# MainBoard.net
KiCad netlist of a schematic drawn in EAGLE
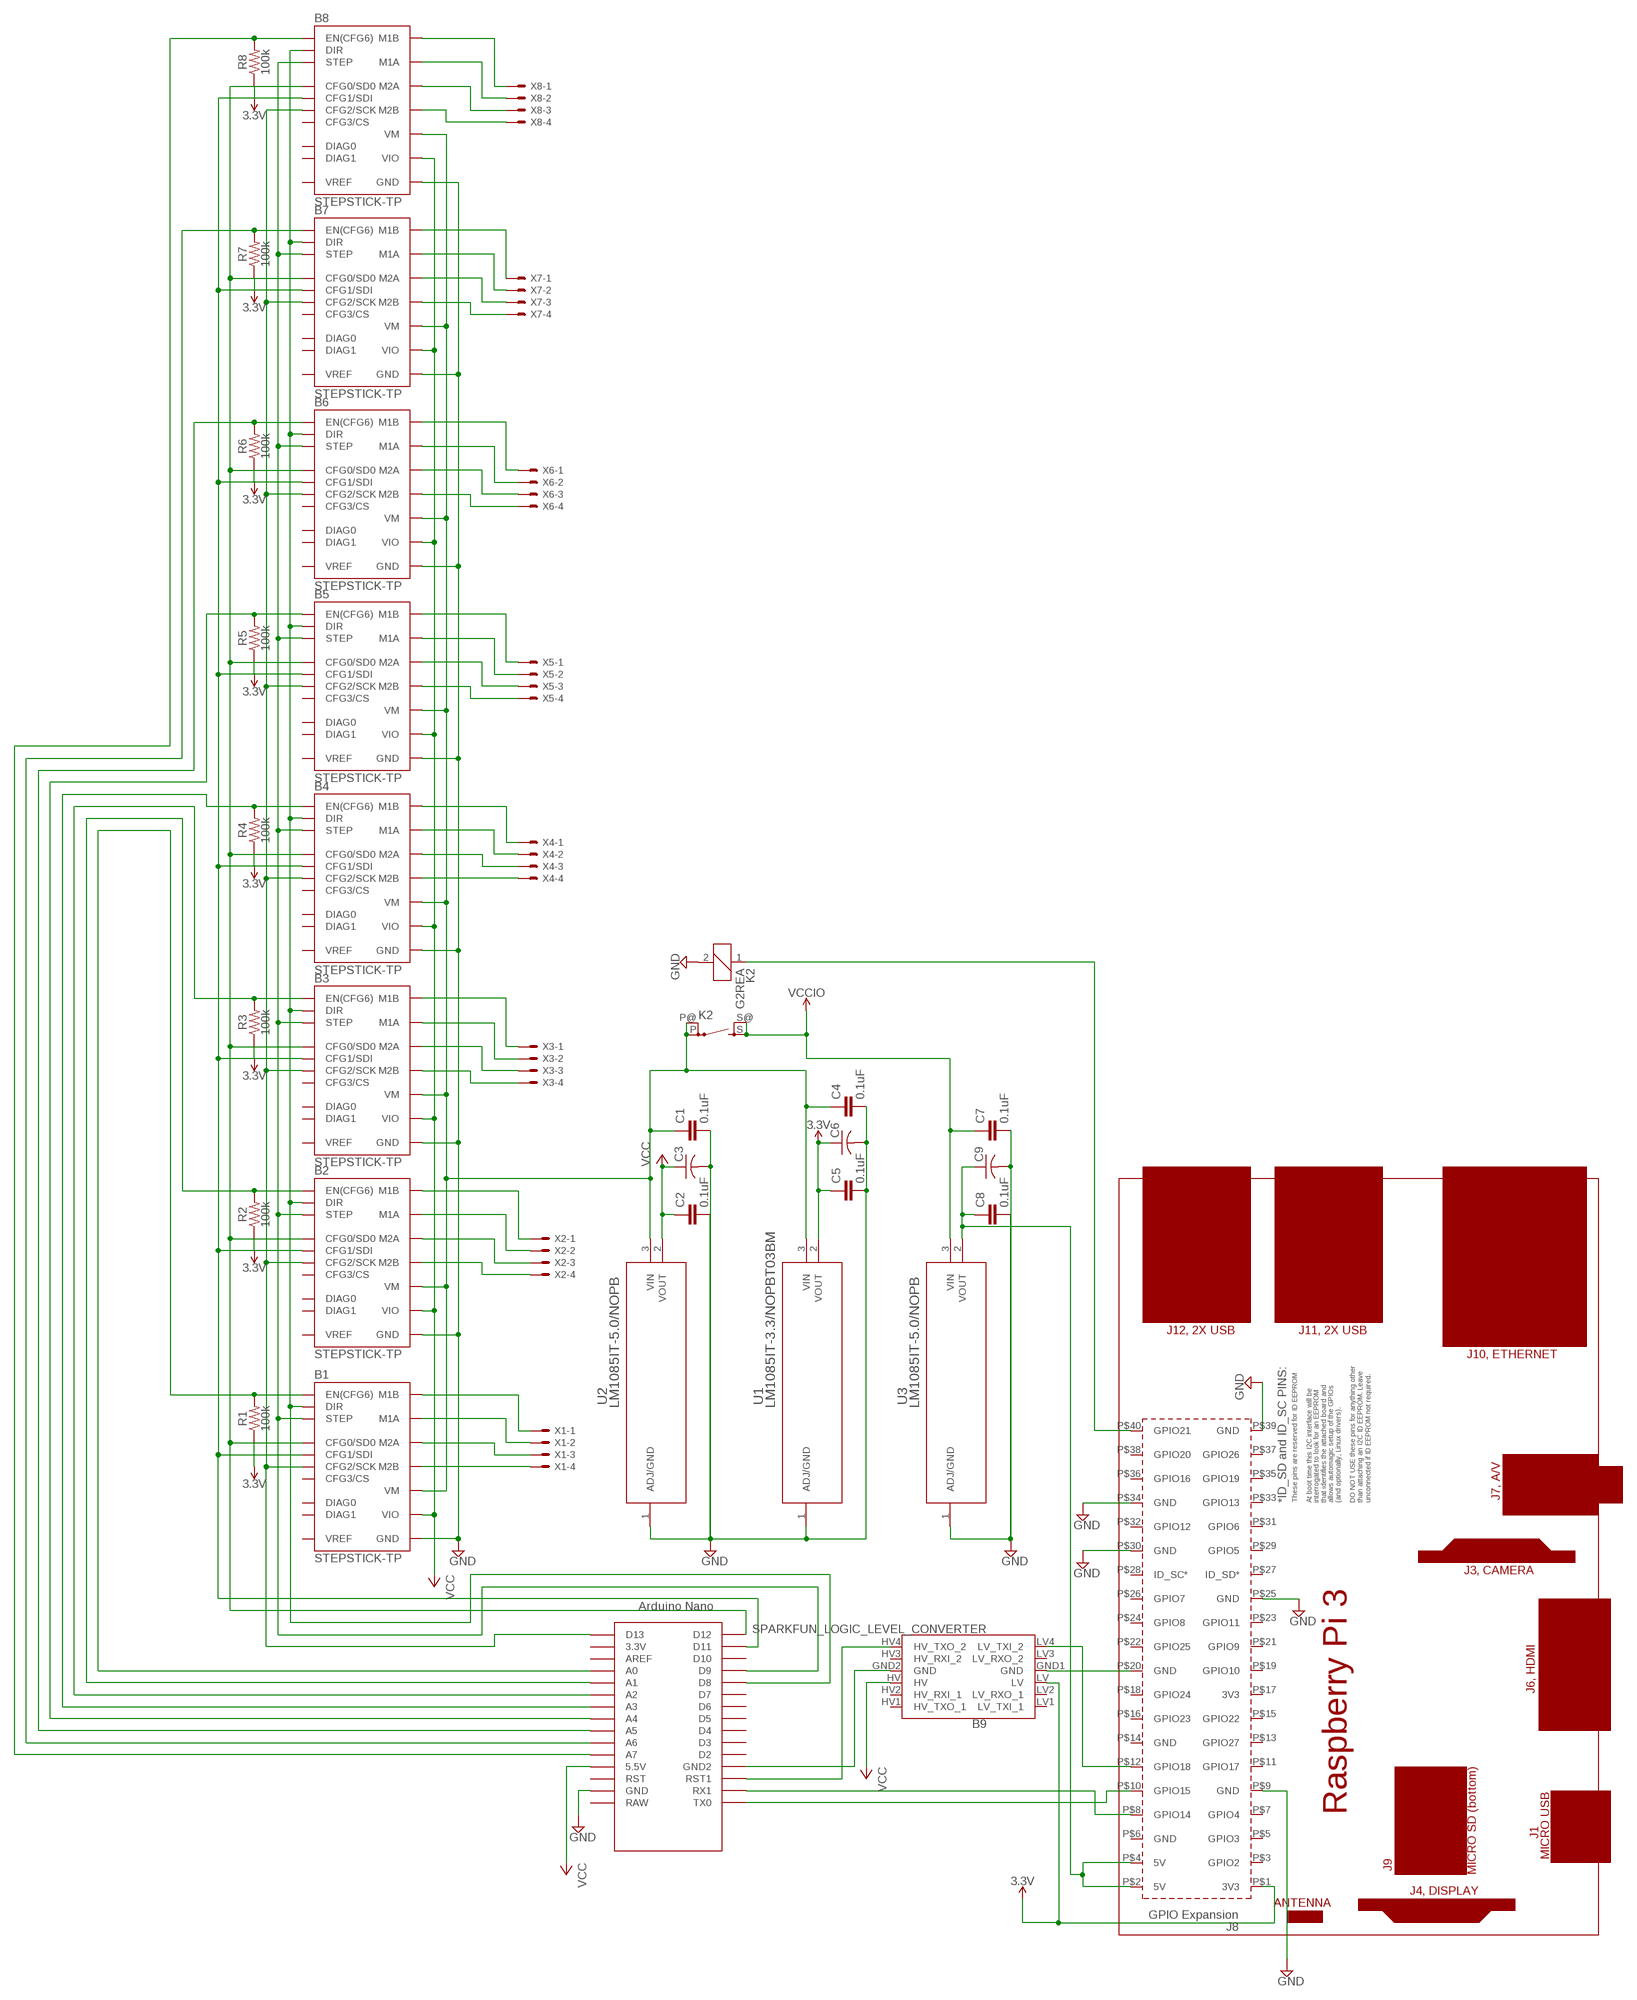
[diagram p0: schematic, sheet 1]

(export (version "E")
  (design (tool "Eeschema 10.0.6"))
  (components
    (comp (ref "B1")
      (value "STEPSTICK-TP")
      (footprint "eagle-import:STEPSTICK_TP")
      (libsource (lib "eagle-import") (part "STEPSTICK-TP"))
    )
    (comp (ref "B2")
      (value "STEPSTICK-TP")
      (footprint "eagle-import:STEPSTICK_TP")
      (libsource (lib "eagle-import") (part "STEPSTICK-TP"))
    )
    (comp (ref "B3")
      (value "STEPSTICK-TP")
      (footprint "eagle-import:STEPSTICK_TP")
      (libsource (lib "eagle-import") (part "STEPSTICK-TP"))
    )
    (comp (ref "B4")
      (value "STEPSTICK-TP")
      (footprint "eagle-import:STEPSTICK_TP")
      (libsource (lib "eagle-import") (part "STEPSTICK-TP"))
    )
    (comp (ref "B5")
      (value "STEPSTICK-TP")
      (footprint "eagle-import:STEPSTICK_TP")
      (libsource (lib "eagle-import") (part "STEPSTICK-TP"))
    )
    (comp (ref "B6")
      (value "STEPSTICK-TP")
      (footprint "eagle-import:STEPSTICK_TP")
      (libsource (lib "eagle-import") (part "STEPSTICK-TP"))
    )
    (comp (ref "B7")
      (value "STEPSTICK-TP")
      (footprint "eagle-import:STEPSTICK_TP")
      (libsource (lib "eagle-import") (part "STEPSTICK-TP"))
    )
    (comp (ref "B8")
      (value "STEPSTICK-TP")
      (footprint "eagle-import:STEPSTICK_TP")
      (libsource (lib "eagle-import") (part "STEPSTICK-TP"))
    )
    (comp (ref "B9")
      (value "SPARKFUN_LOGIC_LEVEL_CONVERTER")
      (footprint "eagle-import:SPARKFUN_LOGIC_LEVEL_CONVERTER")
      (libsource (lib "eagle-import") (part "SPARKFUN_LOGIC_LEVEL_CONVERTER"))
    )
    (comp (ref "C1")
      (value "0.1uF")
      (footprint "eagle-import:CAP-PTH-SMALL-KIT")
      (libsource (lib "eagle-import") (part "0.1UF-KIT-EZ-50V-20%"))
    )
    (comp (ref "C2")
      (value "0.1uF")
      (footprint "eagle-import:CAP-PTH-SMALL-KIT")
      (libsource (lib "eagle-import") (part "0.1UF-KIT-EZ-50V-20%"))
    )
    (comp (ref "C3")
      (value "C-US025-050X050")
      (footprint "eagle-import:C025-050X050")
      (libsource (lib "eagle-import") (part "C-US025-050X050"))
    )
    (comp (ref "C4")
      (value "0.1uF")
      (footprint "eagle-import:CAP-PTH-SMALL-KIT")
      (libsource (lib "eagle-import") (part "0.1UF-KIT-EZ-50V-20%"))
    )
    (comp (ref "C5")
      (value "0.1uF")
      (footprint "eagle-import:CAP-PTH-SMALL-KIT")
      (libsource (lib "eagle-import") (part "0.1UF-KIT-EZ-50V-20%"))
    )
    (comp (ref "C6")
      (value "C-US025-050X050")
      (footprint "eagle-import:C025-050X050")
      (libsource (lib "eagle-import") (part "C-US025-050X050"))
    )
    (comp (ref "C7")
      (value "0.1uF")
      (footprint "eagle-import:CAP-PTH-SMALL-KIT")
      (libsource (lib "eagle-import") (part "0.1UF-KIT-EZ-50V-20%"))
    )
    (comp (ref "C8")
      (value "0.1uF")
      (footprint "eagle-import:CAP-PTH-SMALL-KIT")
      (libsource (lib "eagle-import") (part "0.1UF-KIT-EZ-50V-20%"))
    )
    (comp (ref "C9")
      (value "C-US025-050X050")
      (footprint "eagle-import:C025-050X050")
      (libsource (lib "eagle-import") (part "C-US025-050X050"))
    )
    (comp (ref "K2")
      (value "G2REA")
      (footprint "eagle-import:G2REA")
      (libsource (lib "eagle-import") (part "G2REA"))
    )
    (comp (ref "PCB1")
      (value "RPI3")
      (footprint "eagle-import:RPI3")
      (libsource (lib "eagle-import") (part "RPI3"))
    )
    (comp (ref "R1")
      (value "100k")
      (footprint "eagle-import:AXIAL-0.3-KIT")
      (libsource (lib "eagle-import") (part "100KOHM-HORIZ_KIT-1/4W-5%"))
    )
    (comp (ref "R2")
      (value "100k")
      (footprint "eagle-import:AXIAL-0.3-KIT")
      (libsource (lib "eagle-import") (part "100KOHM-HORIZ_KIT-1/4W-5%"))
    )
    (comp (ref "R3")
      (value "100k")
      (footprint "eagle-import:AXIAL-0.3-KIT")
      (libsource (lib "eagle-import") (part "100KOHM-HORIZ_KIT-1/4W-5%"))
    )
    (comp (ref "R4")
      (value "100k")
      (footprint "eagle-import:AXIAL-0.3-KIT")
      (libsource (lib "eagle-import") (part "100KOHM-HORIZ_KIT-1/4W-5%"))
    )
    (comp (ref "R5")
      (value "100k")
      (footprint "eagle-import:AXIAL-0.3-KIT")
      (libsource (lib "eagle-import") (part "100KOHM-HORIZ_KIT-1/4W-5%"))
    )
    (comp (ref "R6")
      (value "100k")
      (footprint "eagle-import:AXIAL-0.3-KIT")
      (libsource (lib "eagle-import") (part "100KOHM-HORIZ_KIT-1/4W-5%"))
    )
    (comp (ref "R7")
      (value "100k")
      (footprint "eagle-import:AXIAL-0.3-KIT")
      (libsource (lib "eagle-import") (part "100KOHM-HORIZ_KIT-1/4W-5%"))
    )
    (comp (ref "R8")
      (value "100k")
      (footprint "eagle-import:AXIAL-0.3-KIT")
      (libsource (lib "eagle-import") (part "100KOHM-HORIZ_KIT-1/4W-5%"))
    )
    (comp (ref "U$1")
      (value "NANO")
      (footprint "eagle-import:NANO")
      (libsource (lib "eagle-import") (part "NANO"))
    )
    (comp (ref "U1")
      (value "LM1085IT-3.3/NOPBT03BM")
      (footprint "eagle-import:T03BM")
      (fields (field (name "MANUFACTURER_PART_NUMBER") "LM1085IT3.3NOPB"))
      (libsource (lib "eagle-import") (part "LM1085IT-3.3/NOPBT03BM"))
    )
    (comp (ref "U2")
      (value "LM1085IT-5.0/NOPB")
      (footprint "eagle-import:T03B")
      (fields (field (name "MANUFACTURER_PART_NUMBER") "LM1085IT5.0NOPB"))
      (libsource (lib "eagle-import") (part "LM1085IT-5.0/NOPB"))
    )
    (comp (ref "U3")
      (value "LM1085IT-5.0/NOPB")
      (footprint "eagle-import:T03B")
      (fields (field (name "MANUFACTURER_PART_NUMBER") "LM1085IT5.0NOPB"))
      (libsource (lib "eagle-import") (part "LM1085IT-5.0/NOPB"))
    )
    (comp (ref "X1")
      (value "KK-156-4")
      (footprint "eagle-import:KK-156-4")
      (fields (field (name "MF") "MOLEX"))
      (libsource (lib "eagle-import") (part "KK-156-4"))
    )
    (comp (ref "X2")
      (value "KK-156-4")
      (footprint "eagle-import:KK-156-4")
      (fields (field (name "MF") "MOLEX"))
      (libsource (lib "eagle-import") (part "KK-156-4"))
    )
    (comp (ref "X3")
      (value "KK-156-4")
      (footprint "eagle-import:KK-156-4")
      (fields (field (name "MF") "MOLEX"))
      (libsource (lib "eagle-import") (part "KK-156-4"))
    )
    (comp (ref "X4")
      (value "KK-156-4")
      (footprint "eagle-import:KK-156-4")
      (fields (field (name "MF") "MOLEX"))
      (libsource (lib "eagle-import") (part "KK-156-4"))
    )
    (comp (ref "X5")
      (value "KK-156-4")
      (footprint "eagle-import:KK-156-4")
      (fields (field (name "MF") "MOLEX"))
      (libsource (lib "eagle-import") (part "KK-156-4"))
    )
    (comp (ref "X6")
      (value "KK-156-4")
      (footprint "eagle-import:KK-156-4")
      (fields (field (name "MF") "MOLEX"))
      (libsource (lib "eagle-import") (part "KK-156-4"))
    )
    (comp (ref "X7")
      (value "KK-156-4")
      (footprint "eagle-import:KK-156-4")
      (fields (field (name "MF") "MOLEX"))
      (libsource (lib "eagle-import") (part "KK-156-4"))
    )
    (comp (ref "X8")
      (value "KK-156-4")
      (footprint "eagle-import:KK-156-4")
      (fields (field (name "MF") "MOLEX"))
      (libsource (lib "eagle-import") (part "KK-156-4"))
    )
  )
  (nets
    (net (code "1") (name "3.3V") (class "Default")
      (node (ref "B9") (pin "LV") (pinfunction "LV_LV") (pintype "power_in"))
      (node (ref "C5") (pin "1") (pinfunction "1_1") (pintype "passive"))
      (node (ref "C6") (pin "1") (pinfunction "1_1") (pintype "passive"))
      (node (ref "PCB1") (pin "P$1") (pinfunction "3V3_P$1") (pintype "bidirectional"))
      (node (ref "R1") (pin "P$1") (pinfunction "1_P$1") (pintype "passive"))
      (node (ref "R2") (pin "P$1") (pinfunction "1_P$1") (pintype "passive"))
      (node (ref "R3") (pin "P$1") (pinfunction "1_P$1") (pintype "passive"))
      (node (ref "R4") (pin "P$1") (pinfunction "1_P$1") (pintype "passive"))
      (node (ref "R5") (pin "P$1") (pinfunction "1_P$1") (pintype "passive"))
      (node (ref "R6") (pin "P$1") (pinfunction "1_P$1") (pintype "passive"))
      (node (ref "R7") (pin "P$1") (pinfunction "1_P$1") (pintype "passive"))
      (node (ref "R8") (pin "P$1") (pinfunction "1_P$1") (pintype "passive"))
      (node (ref "U1") (pin "2") (pinfunction "VOUT_2") (pintype "output"))
    )
    (net (code "2") (name "GND") (class "Default")
      (node (ref "B1") (pin "GND@1") (pinfunction "GND_GND@1") (pintype "power_in"))
      (node (ref "B1") (pin "GND@2") (pinfunction "GND_GND@2") (pintype "power_in"))
      (node (ref "B2") (pin "GND@1") (pinfunction "GND_GND@1") (pintype "power_in"))
      (node (ref "B2") (pin "GND@2") (pinfunction "GND_GND@2") (pintype "power_in"))
      (node (ref "B3") (pin "GND@1") (pinfunction "GND_GND@1") (pintype "power_in"))
      (node (ref "B3") (pin "GND@2") (pinfunction "GND_GND@2") (pintype "power_in"))
      (node (ref "B4") (pin "GND@1") (pinfunction "GND_GND@1") (pintype "power_in"))
      (node (ref "B4") (pin "GND@2") (pinfunction "GND_GND@2") (pintype "power_in"))
      (node (ref "B5") (pin "GND@1") (pinfunction "GND_GND@1") (pintype "power_in"))
      (node (ref "B5") (pin "GND@2") (pinfunction "GND_GND@2") (pintype "power_in"))
      (node (ref "B6") (pin "GND@1") (pinfunction "GND_GND@1") (pintype "power_in"))
      (node (ref "B6") (pin "GND@2") (pinfunction "GND_GND@2") (pintype "power_in"))
      (node (ref "B7") (pin "GND@1") (pinfunction "GND_GND@1") (pintype "power_in"))
      (node (ref "B7") (pin "GND@2") (pinfunction "GND_GND@2") (pintype "power_in"))
      (node (ref "B8") (pin "GND@1") (pinfunction "GND_GND@1") (pintype "power_in"))
      (node (ref "B8") (pin "GND@2") (pinfunction "GND_GND@2") (pintype "power_in"))
      (node (ref "C1") (pin "2") (pinfunction "2_2") (pintype "passive"))
      (node (ref "C2") (pin "2") (pinfunction "2_2") (pintype "passive"))
      (node (ref "C3") (pin "2") (pinfunction "2_2") (pintype "passive"))
      (node (ref "C4") (pin "2") (pinfunction "2_2") (pintype "passive"))
      (node (ref "C5") (pin "2") (pinfunction "2_2") (pintype "passive"))
      (node (ref "C6") (pin "2") (pinfunction "2_2") (pintype "passive"))
      (node (ref "C7") (pin "2") (pinfunction "2_2") (pintype "passive"))
      (node (ref "C8") (pin "2") (pinfunction "2_2") (pintype "passive"))
      (node (ref "C9") (pin "2") (pinfunction "2_2") (pintype "passive"))
      (node (ref "K2") (pin "2") (pinfunction "2_2") (pintype "passive"))
      (node (ref "PCB1") (pin "P$25") (pinfunction "GND_P$25") (pintype "bidirectional"))
      (node (ref "PCB1") (pin "P$30") (pinfunction "GND_P$30") (pintype "bidirectional"))
      (node (ref "PCB1") (pin "P$34") (pinfunction "GND_P$34") (pintype "bidirectional"))
      (node (ref "PCB1") (pin "P$39") (pinfunction "GND_P$39") (pintype "bidirectional"))
      (node (ref "PCB1") (pin "P$9") (pinfunction "GND_P$9") (pintype "bidirectional"))
      (node (ref "U$1") (pin "GND") (pinfunction "GND_GND") (pintype "bidirectional"))
      (node (ref "U1") (pin "1") (pinfunction "ADJ/GND_1") (pintype "passive"))
      (node (ref "U2") (pin "1") (pinfunction "ADJ/GND_1") (pintype "passive"))
      (node (ref "U3") (pin "1") (pinfunction "ADJ/GND_1") (pintype "passive"))
    )
    (net (code "3") (name "Net-(B1-CFG0{slash}SD0)") (class "Default")
      (node (ref "B1") (pin "NC/CFG0") (pinfunction "CFG0/SD0_NC/CFG0") (pintype "bidirectional"))
      (node (ref "B2") (pin "NC/CFG0") (pinfunction "CFG0/SD0_NC/CFG0") (pintype "bidirectional"))
      (node (ref "B3") (pin "NC/CFG0") (pinfunction "CFG0/SD0_NC/CFG0") (pintype "bidirectional"))
      (node (ref "B4") (pin "NC/CFG0") (pinfunction "CFG0/SD0_NC/CFG0") (pintype "bidirectional"))
      (node (ref "B5") (pin "NC/CFG0") (pinfunction "CFG0/SD0_NC/CFG0") (pintype "bidirectional"))
      (node (ref "B6") (pin "NC/CFG0") (pinfunction "CFG0/SD0_NC/CFG0") (pintype "bidirectional"))
      (node (ref "B7") (pin "NC/CFG0") (pinfunction "CFG0/SD0_NC/CFG0") (pintype "bidirectional"))
      (node (ref "B8") (pin "NC/CFG0") (pinfunction "CFG0/SD0_NC/CFG0") (pintype "bidirectional"))
      (node (ref "U$1") (pin "D12") (pinfunction "D12_D12") (pintype "bidirectional"))
    )
    (net (code "4") (name "Net-(B1-CFG1{slash}SDI)") (class "Default")
      (node (ref "B1") (pin "CFG1") (pinfunction "CFG1/SDI_CFG1") (pintype "bidirectional"))
      (node (ref "B2") (pin "CFG1") (pinfunction "CFG1/SDI_CFG1") (pintype "bidirectional"))
      (node (ref "B3") (pin "CFG1") (pinfunction "CFG1/SDI_CFG1") (pintype "bidirectional"))
      (node (ref "B4") (pin "CFG1") (pinfunction "CFG1/SDI_CFG1") (pintype "bidirectional"))
      (node (ref "B5") (pin "CFG1") (pinfunction "CFG1/SDI_CFG1") (pintype "bidirectional"))
      (node (ref "B6") (pin "CFG1") (pinfunction "CFG1/SDI_CFG1") (pintype "bidirectional"))
      (node (ref "B7") (pin "CFG1") (pinfunction "CFG1/SDI_CFG1") (pintype "bidirectional"))
      (node (ref "B8") (pin "CFG1") (pinfunction "CFG1/SDI_CFG1") (pintype "bidirectional"))
      (node (ref "U$1") (pin "D11") (pinfunction "D11_D11") (pintype "bidirectional"))
    )
    (net (code "5") (name "Net-(B1-CFG2{slash}SCK)") (class "Default")
      (node (ref "B1") (pin "CFG2") (pinfunction "CFG2/SCK_CFG2") (pintype "bidirectional"))
      (node (ref "B2") (pin "CFG2") (pinfunction "CFG2/SCK_CFG2") (pintype "bidirectional"))
      (node (ref "B3") (pin "CFG2") (pinfunction "CFG2/SCK_CFG2") (pintype "bidirectional"))
      (node (ref "B4") (pin "CFG2") (pinfunction "CFG2/SCK_CFG2") (pintype "bidirectional"))
      (node (ref "B5") (pin "CFG2") (pinfunction "CFG2/SCK_CFG2") (pintype "bidirectional"))
      (node (ref "B6") (pin "CFG2") (pinfunction "CFG2/SCK_CFG2") (pintype "bidirectional"))
      (node (ref "B7") (pin "CFG2") (pinfunction "CFG2/SCK_CFG2") (pintype "bidirectional"))
      (node (ref "B8") (pin "CFG2") (pinfunction "CFG2/SCK_CFG2") (pintype "bidirectional"))
      (node (ref "U$1") (pin "D13") (pinfunction "D13_D13") (pintype "bidirectional"))
    )
    (net (code "6") (name "Net-(B1-EN(CFG6))") (class "Default")
      (node (ref "B1") (pin "EN") (pinfunction "EN(CFG6)_EN") (pintype "bidirectional"))
      (node (ref "R1") (pin "P$2") (pinfunction "2_P$2") (pintype "passive"))
      (node (ref "U$1") (pin "A0") (pinfunction "A0_A0") (pintype "bidirectional"))
    )
    (net (code "7") (name "Net-(B1-PadDIR)") (class "Default")
      (node (ref "B1") (pin "DIR") (pinfunction "DIR_DIR") (pintype "bidirectional"))
      (node (ref "B2") (pin "DIR") (pinfunction "DIR_DIR") (pintype "bidirectional"))
      (node (ref "B3") (pin "DIR") (pinfunction "DIR_DIR") (pintype "bidirectional"))
      (node (ref "B4") (pin "DIR") (pinfunction "DIR_DIR") (pintype "bidirectional"))
      (node (ref "B5") (pin "DIR") (pinfunction "DIR_DIR") (pintype "bidirectional"))
      (node (ref "B6") (pin "DIR") (pinfunction "DIR_DIR") (pintype "bidirectional"))
      (node (ref "B7") (pin "DIR") (pinfunction "DIR_DIR") (pintype "bidirectional"))
      (node (ref "B8") (pin "DIR") (pinfunction "DIR_DIR") (pintype "bidirectional"))
      (node (ref "U$1") (pin "D8") (pinfunction "D8_D8") (pintype "bidirectional"))
    )
    (net (code "8") (name "Net-(B1-PadSTEP)") (class "Default")
      (node (ref "B1") (pin "STEP") (pinfunction "STEP_STEP") (pintype "bidirectional"))
      (node (ref "B2") (pin "STEP") (pinfunction "STEP_STEP") (pintype "bidirectional"))
      (node (ref "B3") (pin "STEP") (pinfunction "STEP_STEP") (pintype "bidirectional"))
      (node (ref "B4") (pin "STEP") (pinfunction "STEP_STEP") (pintype "bidirectional"))
      (node (ref "B5") (pin "STEP") (pinfunction "STEP_STEP") (pintype "bidirectional"))
      (node (ref "B6") (pin "STEP") (pinfunction "STEP_STEP") (pintype "bidirectional"))
      (node (ref "B7") (pin "STEP") (pinfunction "STEP_STEP") (pintype "bidirectional"))
      (node (ref "B8") (pin "STEP") (pinfunction "STEP_STEP") (pintype "bidirectional"))
      (node (ref "U$1") (pin "D9") (pinfunction "D9_D9") (pintype "bidirectional"))
    )
    (net (code "9") (name "Net-(B2-EN(CFG6))") (class "Default")
      (node (ref "B2") (pin "EN") (pinfunction "EN(CFG6)_EN") (pintype "bidirectional"))
      (node (ref "R2") (pin "P$2") (pinfunction "2_P$2") (pintype "passive"))
      (node (ref "U$1") (pin "A1") (pinfunction "A1_A1") (pintype "bidirectional"))
    )
    (net (code "10") (name "Net-(B3-EN(CFG6))") (class "Default")
      (node (ref "B3") (pin "EN") (pinfunction "EN(CFG6)_EN") (pintype "bidirectional"))
      (node (ref "R3") (pin "P$2") (pinfunction "2_P$2") (pintype "passive"))
      (node (ref "U$1") (pin "A2") (pinfunction "A2_A2") (pintype "bidirectional"))
    )
    (net (code "11") (name "Net-(B4-EN(CFG6))") (class "Default")
      (node (ref "B4") (pin "EN") (pinfunction "EN(CFG6)_EN") (pintype "bidirectional"))
      (node (ref "R4") (pin "P$2") (pinfunction "2_P$2") (pintype "passive"))
      (node (ref "U$1") (pin "A3") (pinfunction "A3_A3") (pintype "bidirectional"))
    )
    (net (code "12") (name "Net-(B5-EN(CFG6))") (class "Default")
      (node (ref "B5") (pin "EN") (pinfunction "EN(CFG6)_EN") (pintype "bidirectional"))
      (node (ref "R5") (pin "P$2") (pinfunction "2_P$2") (pintype "passive"))
      (node (ref "U$1") (pin "A4") (pinfunction "A4_A4") (pintype "bidirectional"))
    )
    (net (code "13") (name "Net-(B6-EN(CFG6))") (class "Default")
      (node (ref "B6") (pin "EN") (pinfunction "EN(CFG6)_EN") (pintype "bidirectional"))
      (node (ref "R6") (pin "P$2") (pinfunction "2_P$2") (pintype "passive"))
      (node (ref "U$1") (pin "A5") (pinfunction "A5_A5") (pintype "bidirectional"))
    )
    (net (code "14") (name "Net-(B7-EN(CFG6))") (class "Default")
      (node (ref "B7") (pin "EN") (pinfunction "EN(CFG6)_EN") (pintype "bidirectional"))
      (node (ref "R7") (pin "P$2") (pinfunction "2_P$2") (pintype "passive"))
      (node (ref "U$1") (pin "A6") (pinfunction "A6_A6") (pintype "bidirectional"))
    )
    (net (code "15") (name "Net-(B8-EN(CFG6))") (class "Default")
      (node (ref "B8") (pin "EN") (pinfunction "EN(CFG6)_EN") (pintype "bidirectional"))
      (node (ref "R8") (pin "P$2") (pinfunction "2_P$2") (pintype "passive"))
      (node (ref "U$1") (pin "A7") (pinfunction "A7_A7") (pintype "bidirectional"))
    )
    (net (code "16") (name "Net-(B9-GND-PadGND1)") (class "Default")
      (node (ref "B9") (pin "GND1") (pinfunction "GND_GND1") (pintype "power_in"))
      (node (ref "PCB1") (pin "P$20") (pinfunction "GND_P$20") (pintype "bidirectional"))
    )
    (net (code "17") (name "Net-(B9-HV_TXO_2)") (class "Default")
      (node (ref "B9") (pin "HV4") (pinfunction "HV_TXO_2_HV4") (pintype "bidirectional"))
      (node (ref "U$1") (pin "RST1") (pinfunction "RST1_RST1") (pintype "bidirectional"))
    )
    (net (code "18") (name "Net-(B9-LV_TXI_2)") (class "Default")
      (node (ref "B9") (pin "LV4") (pinfunction "LV_TXI_2_LV4") (pintype "bidirectional"))
      (node (ref "PCB1") (pin "P$12") (pinfunction "GPIO18_P$12") (pintype "bidirectional"))
    )
    (net (code "19") (name "Net-(PCB1-GPIO14)") (class "Default")
      (node (ref "PCB1") (pin "P$8") (pinfunction "GPIO14_P$8") (pintype "bidirectional"))
      (node (ref "U$1") (pin "RX1") (pinfunction "RX1_RX1") (pintype "bidirectional"))
    )
    (net (code "20") (name "Net-(PCB1-GPIO15)") (class "Default")
      (node (ref "PCB1") (pin "P$10") (pinfunction "GPIO15_P$10") (pintype "bidirectional"))
      (node (ref "U$1") (pin "TX0") (pinfunction "TX0_TX0") (pintype "bidirectional"))
    )
    (net (code "21") (name "Net-(PCB1-GPIO21)") (class "Default")
      (node (ref "K2") (pin "1") (pinfunction "1_1") (pintype "passive"))
      (node (ref "PCB1") (pin "P$40") (pinfunction "GPIO21_P$40") (pintype "bidirectional"))
    )
    (net (code "22") (name "Net-(U$1-GND2)") (class "Default")
      (node (ref "B9") (pin "GND2") (pinfunction "GND_GND2") (pintype "power_in"))
      (node (ref "U$1") (pin "GND1") (pinfunction "GND2_GND1") (pintype "bidirectional"))
    )
    (net (code "23") (name "Net-(U1-VIN)") (class "Default")
      (node (ref "B1") (pin "VM") (pinfunction "VM_VM") (pintype "power_in"))
      (node (ref "B2") (pin "VM") (pinfunction "VM_VM") (pintype "power_in"))
      (node (ref "B3") (pin "VM") (pinfunction "VM_VM") (pintype "power_in"))
      (node (ref "B4") (pin "VM") (pinfunction "VM_VM") (pintype "power_in"))
      (node (ref "B5") (pin "VM") (pinfunction "VM_VM") (pintype "power_in"))
      (node (ref "B6") (pin "VM") (pinfunction "VM_VM") (pintype "power_in"))
      (node (ref "B7") (pin "VM") (pinfunction "VM_VM") (pintype "power_in"))
      (node (ref "B8") (pin "VM") (pinfunction "VM_VM") (pintype "power_in"))
      (node (ref "C1") (pin "1") (pinfunction "1_1") (pintype "passive"))
      (node (ref "C4") (pin "1") (pinfunction "1_1") (pintype "passive"))
      (node (ref "K2") (pin "P") (pinfunction "P_P") (pintype "passive"))
      (node (ref "K2") (pin "P@") (pinfunction "P_P@") (pintype "passive"))
      (node (ref "U1") (pin "3") (pinfunction "VIN_3") (pintype "input"))
      (node (ref "U2") (pin "3") (pinfunction "VIN_3") (pintype "input"))
    )
    (net (code "24") (name "Net-(U3-VOUT)") (class "Default")
      (node (ref "C8") (pin "1") (pinfunction "1_1") (pintype "passive"))
      (node (ref "C9") (pin "1") (pinfunction "1_1") (pintype "passive"))
      (node (ref "PCB1") (pin "P$2") (pinfunction "5V_P$2") (pintype "bidirectional"))
      (node (ref "PCB1") (pin "P$4") (pinfunction "5V_P$4") (pintype "bidirectional"))
      (node (ref "U3") (pin "2") (pinfunction "VOUT_2") (pintype "output"))
    )
    (net (code "25") (name "Net-(X1A-S)") (class "Default")
      (node (ref "B1") (pin "M1B") (pinfunction "M1B_M1B") (pintype "output"))
      (node (ref "X1") (pin "1") (pinfunction "S_1") (pintype "passive"))
    )
    (net (code "26") (name "Net-(X1B-S)") (class "Default")
      (node (ref "B1") (pin "M1A") (pinfunction "M1A_M1A") (pintype "output"))
      (node (ref "X1") (pin "2") (pinfunction "S_2") (pintype "passive"))
    )
    (net (code "27") (name "Net-(X1C-S)") (class "Default")
      (node (ref "B1") (pin "M2A") (pinfunction "M2A_M2A") (pintype "output"))
      (node (ref "X1") (pin "3") (pinfunction "S_3") (pintype "passive"))
    )
    (net (code "28") (name "Net-(X1D-S)") (class "Default")
      (node (ref "B1") (pin "M2B") (pinfunction "M2B_M2B") (pintype "output"))
      (node (ref "X1") (pin "4") (pinfunction "S_4") (pintype "passive"))
    )
    (net (code "29") (name "Net-(X2A-S)") (class "Default")
      (node (ref "B2") (pin "M1B") (pinfunction "M1B_M1B") (pintype "output"))
      (node (ref "X2") (pin "1") (pinfunction "S_1") (pintype "passive"))
    )
    (net (code "30") (name "Net-(X2B-S)") (class "Default")
      (node (ref "B2") (pin "M1A") (pinfunction "M1A_M1A") (pintype "output"))
      (node (ref "X2") (pin "2") (pinfunction "S_2") (pintype "passive"))
    )
    (net (code "31") (name "Net-(X2C-S)") (class "Default")
      (node (ref "B2") (pin "M2A") (pinfunction "M2A_M2A") (pintype "output"))
      (node (ref "X2") (pin "3") (pinfunction "S_3") (pintype "passive"))
    )
    (net (code "32") (name "Net-(X2D-S)") (class "Default")
      (node (ref "B2") (pin "M2B") (pinfunction "M2B_M2B") (pintype "output"))
      (node (ref "X2") (pin "4") (pinfunction "S_4") (pintype "passive"))
    )
    (net (code "33") (name "Net-(X3A-S)") (class "Default")
      (node (ref "B3") (pin "M1B") (pinfunction "M1B_M1B") (pintype "output"))
      (node (ref "X3") (pin "1") (pinfunction "S_1") (pintype "passive"))
    )
    (net (code "34") (name "Net-(X3B-S)") (class "Default")
      (node (ref "B3") (pin "M1A") (pinfunction "M1A_M1A") (pintype "output"))
      (node (ref "X3") (pin "2") (pinfunction "S_2") (pintype "passive"))
    )
    (net (code "35") (name "Net-(X3C-S)") (class "Default")
      (node (ref "B3") (pin "M2A") (pinfunction "M2A_M2A") (pintype "output"))
      (node (ref "X3") (pin "3") (pinfunction "S_3") (pintype "passive"))
    )
    (net (code "36") (name "Net-(X3D-S)") (class "Default")
      (node (ref "B3") (pin "M2B") (pinfunction "M2B_M2B") (pintype "output"))
      (node (ref "X3") (pin "4") (pinfunction "S_4") (pintype "passive"))
    )
    (net (code "37") (name "Net-(X4A-S)") (class "Default")
      (node (ref "B4") (pin "M1B") (pinfunction "M1B_M1B") (pintype "output"))
      (node (ref "X4") (pin "1") (pinfunction "S_1") (pintype "passive"))
    )
    (net (code "38") (name "Net-(X4B-S)") (class "Default")
      (node (ref "B4") (pin "M1A") (pinfunction "M1A_M1A") (pintype "output"))
      (node (ref "X4") (pin "2") (pinfunction "S_2") (pintype "passive"))
    )
    (net (code "39") (name "Net-(X4C-S)") (class "Default")
      (node (ref "B4") (pin "M2A") (pinfunction "M2A_M2A") (pintype "output"))
      (node (ref "X4") (pin "3") (pinfunction "S_3") (pintype "passive"))
    )
    (net (code "40") (name "Net-(X4D-S)") (class "Default")
      (node (ref "B4") (pin "M2B") (pinfunction "M2B_M2B") (pintype "output"))
      (node (ref "X4") (pin "4") (pinfunction "S_4") (pintype "passive"))
    )
    (net (code "41") (name "Net-(X5A-S)") (class "Default")
      (node (ref "B5") (pin "M1B") (pinfunction "M1B_M1B") (pintype "output"))
      (node (ref "X5") (pin "1") (pinfunction "S_1") (pintype "passive"))
    )
    (net (code "42") (name "Net-(X5B-S)") (class "Default")
      (node (ref "B5") (pin "M1A") (pinfunction "M1A_M1A") (pintype "output"))
      (node (ref "X5") (pin "2") (pinfunction "S_2") (pintype "passive"))
    )
    (net (code "43") (name "Net-(X5C-S)") (class "Default")
      (node (ref "B5") (pin "M2A") (pinfunction "M2A_M2A") (pintype "output"))
      (node (ref "X5") (pin "3") (pinfunction "S_3") (pintype "passive"))
    )
    (net (code "44") (name "Net-(X5D-S)") (class "Default")
      (node (ref "B5") (pin "M2B") (pinfunction "M2B_M2B") (pintype "output"))
      (node (ref "X5") (pin "4") (pinfunction "S_4") (pintype "passive"))
    )
    (net (code "45") (name "Net-(X6A-S)") (class "Default")
      (node (ref "B6") (pin "M1B") (pinfunction "M1B_M1B") (pintype "output"))
      (node (ref "X6") (pin "1") (pinfunction "S_1") (pintype "passive"))
    )
    (net (code "46") (name "Net-(X6B-S)") (class "Default")
      (node (ref "B6") (pin "M1A") (pinfunction "M1A_M1A") (pintype "output"))
      (node (ref "X6") (pin "2") (pinfunction "S_2") (pintype "passive"))
    )
    (net (code "47") (name "Net-(X6C-S)") (class "Default")
      (node (ref "B6") (pin "M2A") (pinfunction "M2A_M2A") (pintype "output"))
      (node (ref "X6") (pin "3") (pinfunction "S_3") (pintype "passive"))
    )
    (net (code "48") (name "Net-(X6D-S)") (class "Default")
      (node (ref "B6") (pin "M2B") (pinfunction "M2B_M2B") (pintype "output"))
      (node (ref "X6") (pin "4") (pinfunction "S_4") (pintype "passive"))
    )
    (net (code "49") (name "Net-(X7A-S)") (class "Default")
      (node (ref "B7") (pin "M1B") (pinfunction "M1B_M1B") (pintype "output"))
      (node (ref "X7") (pin "1") (pinfunction "S_1") (pintype "passive"))
    )
    (net (code "50") (name "Net-(X7B-S)") (class "Default")
      (node (ref "B7") (pin "M1A") (pinfunction "M1A_M1A") (pintype "output"))
      (node (ref "X7") (pin "2") (pinfunction "S_2") (pintype "passive"))
    )
    (net (code "51") (name "Net-(X7C-S)") (class "Default")
      (node (ref "B7") (pin "M2A") (pinfunction "M2A_M2A") (pintype "output"))
      (node (ref "X7") (pin "3") (pinfunction "S_3") (pintype "passive"))
    )
    (net (code "52") (name "Net-(X7D-S)") (class "Default")
      (node (ref "B7") (pin "M2B") (pinfunction "M2B_M2B") (pintype "output"))
      (node (ref "X7") (pin "4") (pinfunction "S_4") (pintype "passive"))
    )
    (net (code "53") (name "Net-(X8A-S)") (class "Default")
      (node (ref "B8") (pin "M1B") (pinfunction "M1B_M1B") (pintype "output"))
      (node (ref "X8") (pin "1") (pinfunction "S_1") (pintype "passive"))
    )
    (net (code "54") (name "Net-(X8B-S)") (class "Default")
      (node (ref "B8") (pin "M1A") (pinfunction "M1A_M1A") (pintype "output"))
      (node (ref "X8") (pin "2") (pinfunction "S_2") (pintype "passive"))
    )
    (net (code "55") (name "Net-(X8C-S)") (class "Default")
      (node (ref "B8") (pin "M2A") (pinfunction "M2A_M2A") (pintype "output"))
      (node (ref "X8") (pin "3") (pinfunction "S_3") (pintype "passive"))
    )
    (net (code "56") (name "Net-(X8D-S)") (class "Default")
      (node (ref "B8") (pin "M2B") (pinfunction "M2B_M2B") (pintype "output"))
      (node (ref "X8") (pin "4") (pinfunction "S_4") (pintype "passive"))
    )
    (net (code "57") (name "VCC") (class "Default")
      (node (ref "B1") (pin "VIO") (pinfunction "VIO_VIO") (pintype "power_in"))
      (node (ref "B2") (pin "VIO") (pinfunction "VIO_VIO") (pintype "power_in"))
      (node (ref "B3") (pin "VIO") (pinfunction "VIO_VIO") (pintype "power_in"))
      (node (ref "B4") (pin "VIO") (pinfunction "VIO_VIO") (pintype "power_in"))
      (node (ref "B5") (pin "VIO") (pinfunction "VIO_VIO") (pintype "power_in"))
      (node (ref "B6") (pin "VIO") (pinfunction "VIO_VIO") (pintype "power_in"))
      (node (ref "B7") (pin "VIO") (pinfunction "VIO_VIO") (pintype "power_in"))
      (node (ref "B8") (pin "VIO") (pinfunction "VIO_VIO") (pintype "power_in"))
      (node (ref "B9") (pin "HV") (pinfunction "HV_HV") (pintype "power_in"))
      (node (ref "C2") (pin "1") (pinfunction "1_1") (pintype "passive"))
      (node (ref "C3") (pin "1") (pinfunction "1_1") (pintype "passive"))
      (node (ref "U$1") (pin "5V") (pinfunction "5.5V_5V") (pintype "bidirectional"))
      (node (ref "U2") (pin "2") (pinfunction "VOUT_2") (pintype "output"))
    )
    (net (code "58") (name "VCCIO") (class "Default")
      (node (ref "C7") (pin "1") (pinfunction "1_1") (pintype "passive"))
      (node (ref "K2") (pin "S") (pinfunction "S_S") (pintype "passive"))
      (node (ref "K2") (pin "S@") (pinfunction "S_S@") (pintype "passive"))
      (node (ref "U3") (pin "3") (pinfunction "VIN_3") (pintype "input"))
    )
    (net (code "59") (name "unconnected-(B1-CFG3{slash}CS-PadCFG3)") (class "Default")
      (node (ref "B1") (pin "CFG3") (pinfunction "CFG3/CS_CFG3") (pintype "bidirectional"))
    )
    (net (code "60") (name "unconnected-(B1-PadDIAG0)") (class "Default")
      (node (ref "B1") (pin "DIAG0") (pinfunction "DIAG0_DIAG0") (pintype "bidirectional"))
    )
    (net (code "61") (name "unconnected-(B1-PadDIAG1)") (class "Default")
      (node (ref "B1") (pin "DIAG1") (pinfunction "DIAG1_DIAG1") (pintype "bidirectional"))
    )
    (net (code "62") (name "unconnected-(B1-PadVREF)") (class "Default")
      (node (ref "B1") (pin "VREF") (pinfunction "VREF_VREF") (pintype "passive"))
    )
    (net (code "63") (name "unconnected-(B2-CFG3{slash}CS-PadCFG3)") (class "Default")
      (node (ref "B2") (pin "CFG3") (pinfunction "CFG3/CS_CFG3") (pintype "bidirectional"))
    )
    (net (code "64") (name "unconnected-(B2-PadDIAG0)") (class "Default")
      (node (ref "B2") (pin "DIAG0") (pinfunction "DIAG0_DIAG0") (pintype "bidirectional"))
    )
    (net (code "65") (name "unconnected-(B2-PadDIAG1)") (class "Default")
      (node (ref "B2") (pin "DIAG1") (pinfunction "DIAG1_DIAG1") (pintype "bidirectional"))
    )
    (net (code "66") (name "unconnected-(B2-PadVREF)") (class "Default")
      (node (ref "B2") (pin "VREF") (pinfunction "VREF_VREF") (pintype "passive"))
    )
    (net (code "67") (name "unconnected-(B3-CFG3{slash}CS-PadCFG3)") (class "Default")
      (node (ref "B3") (pin "CFG3") (pinfunction "CFG3/CS_CFG3") (pintype "bidirectional"))
    )
    (net (code "68") (name "unconnected-(B3-PadDIAG0)") (class "Default")
      (node (ref "B3") (pin "DIAG0") (pinfunction "DIAG0_DIAG0") (pintype "bidirectional"))
    )
    (net (code "69") (name "unconnected-(B3-PadDIAG1)") (class "Default")
      (node (ref "B3") (pin "DIAG1") (pinfunction "DIAG1_DIAG1") (pintype "bidirectional"))
    )
    (net (code "70") (name "unconnected-(B3-PadVREF)") (class "Default")
      (node (ref "B3") (pin "VREF") (pinfunction "VREF_VREF") (pintype "passive"))
    )
    (net (code "71") (name "unconnected-(B4-CFG3{slash}CS-PadCFG3)") (class "Default")
      (node (ref "B4") (pin "CFG3") (pinfunction "CFG3/CS_CFG3") (pintype "bidirectional"))
    )
    (net (code "72") (name "unconnected-(B4-PadDIAG0)") (class "Default")
      (node (ref "B4") (pin "DIAG0") (pinfunction "DIAG0_DIAG0") (pintype "bidirectional"))
    )
    (net (code "73") (name "unconnected-(B4-PadDIAG1)") (class "Default")
      (node (ref "B4") (pin "DIAG1") (pinfunction "DIAG1_DIAG1") (pintype "bidirectional"))
    )
    (net (code "74") (name "unconnected-(B4-PadVREF)") (class "Default")
      (node (ref "B4") (pin "VREF") (pinfunction "VREF_VREF") (pintype "passive"))
    )
    (net (code "75") (name "unconnected-(B5-CFG3{slash}CS-PadCFG3)") (class "Default")
      (node (ref "B5") (pin "CFG3") (pinfunction "CFG3/CS_CFG3") (pintype "bidirectional"))
    )
    (net (code "76") (name "unconnected-(B5-PadDIAG0)") (class "Default")
      (node (ref "B5") (pin "DIAG0") (pinfunction "DIAG0_DIAG0") (pintype "bidirectional"))
    )
    (net (code "77") (name "unconnected-(B5-PadDIAG1)") (class "Default")
      (node (ref "B5") (pin "DIAG1") (pinfunction "DIAG1_DIAG1") (pintype "bidirectional"))
    )
    (net (code "78") (name "unconnected-(B5-PadVREF)") (class "Default")
      (node (ref "B5") (pin "VREF") (pinfunction "VREF_VREF") (pintype "passive"))
    )
    (net (code "79") (name "unconnected-(B6-CFG3{slash}CS-PadCFG3)") (class "Default")
      (node (ref "B6") (pin "CFG3") (pinfunction "CFG3/CS_CFG3") (pintype "bidirectional"))
    )
    (net (code "80") (name "unconnected-(B6-PadDIAG0)") (class "Default")
      (node (ref "B6") (pin "DIAG0") (pinfunction "DIAG0_DIAG0") (pintype "bidirectional"))
    )
    (net (code "81") (name "unconnected-(B6-PadDIAG1)") (class "Default")
      (node (ref "B6") (pin "DIAG1") (pinfunction "DIAG1_DIAG1") (pintype "bidirectional"))
    )
    (net (code "82") (name "unconnected-(B6-PadVREF)") (class "Default")
      (node (ref "B6") (pin "VREF") (pinfunction "VREF_VREF") (pintype "passive"))
    )
    (net (code "83") (name "unconnected-(B7-CFG3{slash}CS-PadCFG3)") (class "Default")
      (node (ref "B7") (pin "CFG3") (pinfunction "CFG3/CS_CFG3") (pintype "bidirectional"))
    )
    (net (code "84") (name "unconnected-(B7-PadDIAG0)") (class "Default")
      (node (ref "B7") (pin "DIAG0") (pinfunction "DIAG0_DIAG0") (pintype "bidirectional"))
    )
    (net (code "85") (name "unconnected-(B7-PadDIAG1)") (class "Default")
      (node (ref "B7") (pin "DIAG1") (pinfunction "DIAG1_DIAG1") (pintype "bidirectional"))
    )
    (net (code "86") (name "unconnected-(B7-PadVREF)") (class "Default")
      (node (ref "B7") (pin "VREF") (pinfunction "VREF_VREF") (pintype "passive"))
    )
    (net (code "87") (name "unconnected-(B8-CFG3{slash}CS-PadCFG3)") (class "Default")
      (node (ref "B8") (pin "CFG3") (pinfunction "CFG3/CS_CFG3") (pintype "bidirectional"))
    )
    (net (code "88") (name "unconnected-(B8-PadDIAG0)") (class "Default")
      (node (ref "B8") (pin "DIAG0") (pinfunction "DIAG0_DIAG0") (pintype "bidirectional"))
    )
    (net (code "89") (name "unconnected-(B8-PadDIAG1)") (class "Default")
      (node (ref "B8") (pin "DIAG1") (pinfunction "DIAG1_DIAG1") (pintype "bidirectional"))
    )
    (net (code "90") (name "unconnected-(B8-PadVREF)") (class "Default")
      (node (ref "B8") (pin "VREF") (pinfunction "VREF_VREF") (pintype "passive"))
    )
    (net (code "91") (name "unconnected-(B9-HV_RXI_1-PadHV2)") (class "Default")
      (node (ref "B9") (pin "HV2") (pinfunction "HV_RXI_1_HV2") (pintype "bidirectional"))
    )
    (net (code "92") (name "unconnected-(B9-HV_RXI_2-PadHV3)") (class "Default")
      (node (ref "B9") (pin "HV3") (pinfunction "HV_RXI_2_HV3") (pintype "bidirectional"))
    )
    (net (code "93") (name "unconnected-(B9-HV_TXO_1-PadHV1)") (class "Default")
      (node (ref "B9") (pin "HV1") (pinfunction "HV_TXO_1_HV1") (pintype "bidirectional"))
    )
    (net (code "94") (name "unconnected-(B9-LV_RXO_1-PadLV2)") (class "Default")
      (node (ref "B9") (pin "LV2") (pinfunction "LV_RXO_1_LV2") (pintype "bidirectional"))
    )
    (net (code "95") (name "unconnected-(B9-LV_RXO_2-PadLV3)") (class "Default")
      (node (ref "B9") (pin "LV3") (pinfunction "LV_RXO_2_LV3") (pintype "bidirectional"))
    )
    (net (code "96") (name "unconnected-(B9-LV_TXI_1-PadLV1)") (class "Default")
      (node (ref "B9") (pin "LV1") (pinfunction "LV_TXI_1_LV1") (pintype "bidirectional"))
    )
    (net (code "97") (name "unconnected-(PCB1-3V3-PadP$17)") (class "Default")
      (node (ref "PCB1") (pin "P$17") (pinfunction "3V3_P$17") (pintype "bidirectional"))
    )
    (net (code "98") (name "unconnected-(PCB1-GND-PadP$6)") (class "Default")
      (node (ref "PCB1") (pin "P$6") (pinfunction "GND_P$6") (pintype "bidirectional"))
    )
    (net (code "99") (name "unconnected-(PCB1-GND-PadP$14)") (class "Default")
      (node (ref "PCB1") (pin "P$14") (pinfunction "GND_P$14") (pintype "bidirectional"))
    )
    (net (code "100") (name "unconnected-(PCB1-GPIO2-PadP$3)") (class "Default")
      (node (ref "PCB1") (pin "P$3") (pinfunction "GPIO2_P$3") (pintype "bidirectional"))
    )
    (net (code "101") (name "unconnected-(PCB1-GPIO3-PadP$5)") (class "Default")
      (node (ref "PCB1") (pin "P$5") (pinfunction "GPIO3_P$5") (pintype "bidirectional"))
    )
    (net (code "102") (name "unconnected-(PCB1-GPIO4-PadP$7)") (class "Default")
      (node (ref "PCB1") (pin "P$7") (pinfunction "GPIO4_P$7") (pintype "bidirectional"))
    )
    (net (code "103") (name "unconnected-(PCB1-GPIO5-PadP$29)") (class "Default")
      (node (ref "PCB1") (pin "P$29") (pinfunction "GPIO5_P$29") (pintype "bidirectional"))
    )
    (net (code "104") (name "unconnected-(PCB1-GPIO6-PadP$31)") (class "Default")
      (node (ref "PCB1") (pin "P$31") (pinfunction "GPIO6_P$31") (pintype "bidirectional"))
    )
    (net (code "105") (name "unconnected-(PCB1-GPIO7-PadP$26)") (class "Default")
      (node (ref "PCB1") (pin "P$26") (pinfunction "GPIO7_P$26") (pintype "bidirectional"))
    )
    (net (code "106") (name "unconnected-(PCB1-GPIO8-PadP$24)") (class "Default")
      (node (ref "PCB1") (pin "P$24") (pinfunction "GPIO8_P$24") (pintype "bidirectional"))
    )
    (net (code "107") (name "unconnected-(PCB1-GPIO9-PadP$21)") (class "Default")
      (node (ref "PCB1") (pin "P$21") (pinfunction "GPIO9_P$21") (pintype "bidirectional"))
    )
    (net (code "108") (name "unconnected-(PCB1-GPIO10-PadP$19)") (class "Default")
      (node (ref "PCB1") (pin "P$19") (pinfunction "GPIO10_P$19") (pintype "bidirectional"))
    )
    (net (code "109") (name "unconnected-(PCB1-GPIO11-PadP$23)") (class "Default")
      (node (ref "PCB1") (pin "P$23") (pinfunction "GPIO11_P$23") (pintype "bidirectional"))
    )
    (net (code "110") (name "unconnected-(PCB1-GPIO12-PadP$32)") (class "Default")
      (node (ref "PCB1") (pin "P$32") (pinfunction "GPIO12_P$32") (pintype "bidirectional"))
    )
    (net (code "111") (name "unconnected-(PCB1-GPIO13-PadP$33)") (class "Default")
      (node (ref "PCB1") (pin "P$33") (pinfunction "GPIO13_P$33") (pintype "bidirectional"))
    )
    (net (code "112") (name "unconnected-(PCB1-GPIO16-PadP$36)") (class "Default")
      (node (ref "PCB1") (pin "P$36") (pinfunction "GPIO16_P$36") (pintype "bidirectional"))
    )
    (net (code "113") (name "unconnected-(PCB1-GPIO17-PadP$11)") (class "Default")
      (node (ref "PCB1") (pin "P$11") (pinfunction "GPIO17_P$11") (pintype "bidirectional"))
    )
    (net (code "114") (name "unconnected-(PCB1-GPIO19-PadP$35)") (class "Default")
      (node (ref "PCB1") (pin "P$35") (pinfunction "GPIO19_P$35") (pintype "bidirectional"))
    )
    (net (code "115") (name "unconnected-(PCB1-GPIO20-PadP$38)") (class "Default")
      (node (ref "PCB1") (pin "P$38") (pinfunction "GPIO20_P$38") (pintype "bidirectional"))
    )
    (net (code "116") (name "unconnected-(PCB1-GPIO22-PadP$15)") (class "Default")
      (node (ref "PCB1") (pin "P$15") (pinfunction "GPIO22_P$15") (pintype "bidirectional"))
    )
    (net (code "117") (name "unconnected-(PCB1-GPIO23-PadP$16)") (class "Default")
      (node (ref "PCB1") (pin "P$16") (pinfunction "GPIO23_P$16") (pintype "bidirectional"))
    )
    (net (code "118") (name "unconnected-(PCB1-GPIO24-PadP$18)") (class "Default")
      (node (ref "PCB1") (pin "P$18") (pinfunction "GPIO24_P$18") (pintype "bidirectional"))
    )
    (net (code "119") (name "unconnected-(PCB1-GPIO25-PadP$22)") (class "Default")
      (node (ref "PCB1") (pin "P$22") (pinfunction "GPIO25_P$22") (pintype "bidirectional"))
    )
    (net (code "120") (name "unconnected-(PCB1-GPIO26-PadP$37)") (class "Default")
      (node (ref "PCB1") (pin "P$37") (pinfunction "GPIO26_P$37") (pintype "bidirectional"))
    )
    (net (code "121") (name "unconnected-(PCB1-GPIO27-PadP$13)") (class "Default")
      (node (ref "PCB1") (pin "P$13") (pinfunction "GPIO27_P$13") (pintype "bidirectional"))
    )
    (net (code "122") (name "unconnected-(PCB1-ID_SC*-PadP$28)") (class "Default")
      (node (ref "PCB1") (pin "P$28") (pinfunction "ID_SC*_P$28") (pintype "bidirectional"))
    )
    (net (code "123") (name "unconnected-(PCB1-ID_SD*-PadP$27)") (class "Default")
      (node (ref "PCB1") (pin "P$27") (pinfunction "ID_SD*_P$27") (pintype "bidirectional"))
    )
    (net (code "124") (name "unconnected-(U$1-Pad3.3V)") (class "Default")
      (node (ref "U$1") (pin "3.3V") (pinfunction "3.3V_3.3V") (pintype "bidirectional"))
    )
    (net (code "125") (name "unconnected-(U$1-PadAREF)") (class "Default")
      (node (ref "U$1") (pin "AREF") (pinfunction "AREF_AREF") (pintype "bidirectional"))
    )
    (net (code "126") (name "unconnected-(U$1-PadD2)") (class "Default")
      (node (ref "U$1") (pin "D2") (pinfunction "D2_D2") (pintype "bidirectional"))
    )
    (net (code "127") (name "unconnected-(U$1-PadD3)") (class "Default")
      (node (ref "U$1") (pin "D3") (pinfunction "D3_D3") (pintype "bidirectional"))
    )
    (net (code "128") (name "unconnected-(U$1-PadD4)") (class "Default")
      (node (ref "U$1") (pin "D4") (pinfunction "D4_D4") (pintype "bidirectional"))
    )
    (net (code "129") (name "unconnected-(U$1-PadD5)") (class "Default")
      (node (ref "U$1") (pin "D5") (pinfunction "D5_D5") (pintype "bidirectional"))
    )
    (net (code "130") (name "unconnected-(U$1-PadD6)") (class "Default")
      (node (ref "U$1") (pin "D6") (pinfunction "D6_D6") (pintype "bidirectional"))
    )
    (net (code "131") (name "unconnected-(U$1-PadD7)") (class "Default")
      (node (ref "U$1") (pin "D7") (pinfunction "D7_D7") (pintype "bidirectional"))
    )
    (net (code "132") (name "unconnected-(U$1-PadD10)") (class "Default")
      (node (ref "U$1") (pin "D10") (pinfunction "D10_D10") (pintype "bidirectional"))
    )
    (net (code "133") (name "unconnected-(U$1-PadICSP1)") (class "Default")
      (node (ref "U$1") (pin "ICSP1") (pinfunction "ICSP1_ICSP1") (pintype "bidirectional"))
    )
    (net (code "134") (name "unconnected-(U$1-PadICSP2)") (class "Default")
      (node (ref "U$1") (pin "ICSP2") (pinfunction "ICSP2_ICSP2") (pintype "bidirectional"))
    )
    (net (code "135") (name "unconnected-(U$1-PadICSP3)") (class "Default")
      (node (ref "U$1") (pin "ICSP3") (pinfunction "ICSP3_ICSP3") (pintype "bidirectional"))
    )
    (net (code "136") (name "unconnected-(U$1-PadICSP4)") (class "Default")
      (node (ref "U$1") (pin "ICSP4") (pinfunction "ICSP4_ICSP4") (pintype "bidirectional"))
    )
    (net (code "137") (name "unconnected-(U$1-PadICSP5)") (class "Default")
      (node (ref "U$1") (pin "ICSP5") (pinfunction "ICSP5_ICSP5") (pintype "bidirectional"))
    )
    (net (code "138") (name "unconnected-(U$1-PadICSP6)") (class "Default")
      (node (ref "U$1") (pin "ICSP6") (pinfunction "ICSP6_ICSP6") (pintype "bidirectional"))
    )
    (net (code "139") (name "unconnected-(U$1-PadRAW)") (class "Default")
      (node (ref "U$1") (pin "RAW") (pinfunction "RAW_RAW") (pintype "bidirectional"))
    )
    (net (code "140") (name "unconnected-(U$1-PadRST)") (class "Default")
      (node (ref "U$1") (pin "RST") (pinfunction "RST_RST") (pintype "bidirectional"))
    )
  )
)
